# 05_Wireless.net
KiCad netlist of a schematic drawn in Altium Designer
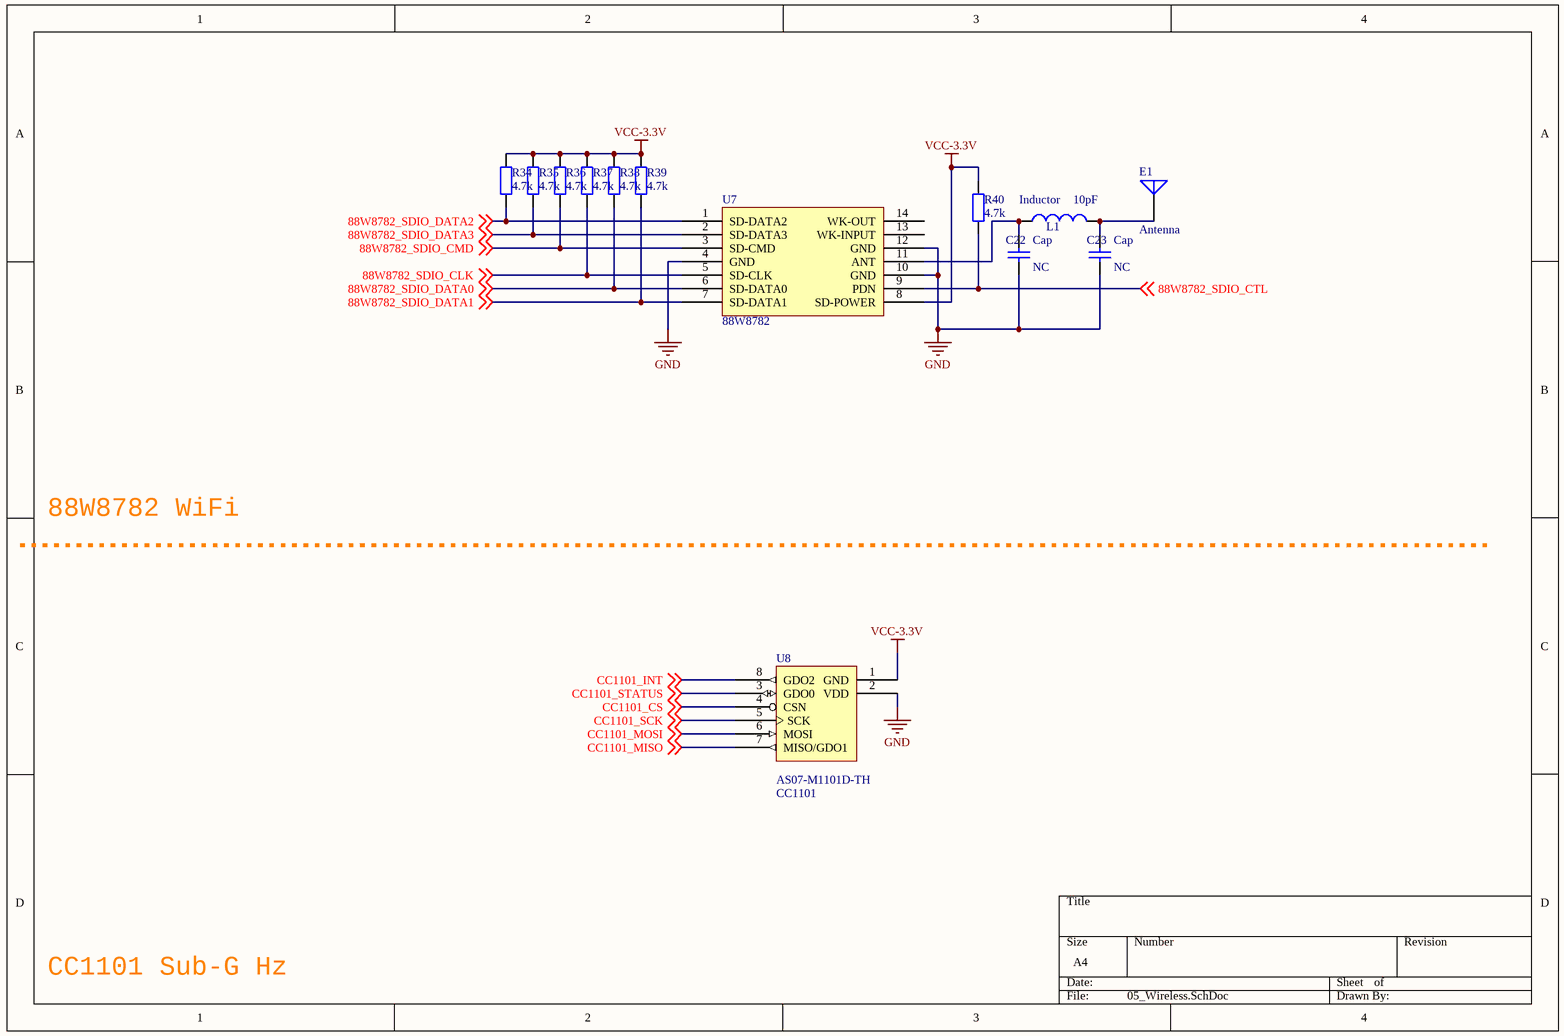
[diagram p0: 05_Wireless.SchDoc]

(export (version "E")
  (design (tool "Eeschema 10.0.6"))
  (components
    (comp (ref "C22")
      (value "Cap")
      (footprint "RAD-0.1")
      (description "Capacitor")
      (fields (field (name "ALTIUM_VALUE") "NC") (field (name "PUBLISHER") "Altium Limited"))
      (libsource (lib "Miscellaneous Devices") (part "Cap"))
    )
    (comp (ref "C23")
      (value "Cap")
      (footprint "RAD-0.1")
      (description "Capacitor")
      (fields (field (name "ALTIUM_VALUE") "NC") (field (name "PUBLISHER") "Altium Limited"))
      (libsource (lib "Miscellaneous Devices") (part "Cap"))
    )
    (comp (ref "E1")
      (value "Antenna")
      (footprint "ANT_MEANDER_LINE")
      (description "Generic Antenna")
      (fields (field (name "PUBLISHER") "Altium Limited"))
      (libsource (lib "Miscellaneous Devices") (part "Antenna"))
    )
    (comp (ref "L1")
      (value "Inductor")
      (footprint "0603")
      (fields (field (name "ALTIUM_VALUE") "10pF") (field (name "PUBLISHER") "Altium Limited"))
      (libsource (lib "Miscellaneous Devices") (part "Inductor"))
    )
    (comp (ref "R34")
      (value "4.7k")
      (footprint "AXIAL-0.3")
      (description "贴片电阻")
      (fields (field (name "Comment") "10k") (field (name "PUBLISHER") "Altium Limited"))
      (libsource (lib "fszhang") (part "Res1"))
    )
    (comp (ref "R35")
      (value "4.7k")
      (footprint "AXIAL-0.3")
      (description "贴片电阻")
      (fields (field (name "Comment") "10k") (field (name "PUBLISHER") "Altium Limited"))
      (libsource (lib "fszhang") (part "Res1"))
    )
    (comp (ref "R36")
      (value "4.7k")
      (footprint "AXIAL-0.3")
      (description "贴片电阻")
      (fields (field (name "Comment") "10k") (field (name "PUBLISHER") "Altium Limited"))
      (libsource (lib "fszhang") (part "Res1"))
    )
    (comp (ref "R37")
      (value "4.7k")
      (footprint "AXIAL-0.3")
      (description "贴片电阻")
      (fields (field (name "Comment") "10k") (field (name "PUBLISHER") "Altium Limited"))
      (libsource (lib "fszhang") (part "Res1"))
    )
    (comp (ref "R38")
      (value "4.7k")
      (footprint "AXIAL-0.3")
      (description "贴片电阻")
      (fields (field (name "Comment") "10k") (field (name "PUBLISHER") "Altium Limited"))
      (libsource (lib "fszhang") (part "Res1"))
    )
    (comp (ref "R39")
      (value "4.7k")
      (footprint "AXIAL-0.3")
      (description "贴片电阻")
      (fields (field (name "Comment") "10k") (field (name "PUBLISHER") "Altium Limited"))
      (libsource (lib "fszhang") (part "Res1"))
    )
    (comp (ref "R40")
      (value "4.7k")
      (footprint "AXIAL-0.3")
      (description "贴片电阻")
      (fields (field (name "Comment") "10k") (field (name "PUBLISHER") "Altium Limited"))
      (libsource (lib "fszhang") (part "Res1"))
    )
    (comp (ref "U7")
      (value "88W8782")
      (footprint "W8782")
      (description "802.11n Wireless Module")
      (libsource (lib "Miscellaneous Modules") (part "88W8782"))
    )
    (comp (ref "U8")
      (value "CC1101")
      (footprint "AS07-M1101D-TH")
      (fields
        (field (name "MANUFACTURER") "Texas Instruments (TI)")
        (field (name "MANUFACTURER PART NUMBER") "CC1101RGP")
      )
      (libsource (lib "Miscellaneous Modules") (part "CC1101"))
    )
  )
  (nets
    (net (code "1") (name "88W8782_SDIO_CLK") (class "Default")
      (node (ref "R37") (pin "1") (pinfunction "1_1") (pintype "passive"))
      (node (ref "U7") (pin "5") (pinfunction "SD-CLK_5") (pintype "passive"))
    )
    (net (code "2") (name "88W8782_SDIO_CMD") (class "Default")
      (node (ref "R36") (pin "1") (pinfunction "1_1") (pintype "passive"))
      (node (ref "U7") (pin "3") (pinfunction "SD-CMD_3") (pintype "passive"))
    )
    (net (code "3") (name "88W8782_SDIO_CTL") (class "Default")
      (node (ref "R40") (pin "1") (pinfunction "1_1") (pintype "passive"))
      (node (ref "U7") (pin "9") (pinfunction "PDN_9") (pintype "passive"))
    )
    (net (code "4") (name "88W8782_SDIO_DATA0") (class "Default")
      (node (ref "R38") (pin "1") (pinfunction "1_1") (pintype "passive"))
      (node (ref "U7") (pin "6") (pinfunction "SD-DATA0_6") (pintype "passive"))
    )
    (net (code "5") (name "88W8782_SDIO_DATA1") (class "Default")
      (node (ref "R39") (pin "1") (pinfunction "1_1") (pintype "passive"))
      (node (ref "U7") (pin "7") (pinfunction "SD-DATA1_7") (pintype "passive"))
    )
    (net (code "6") (name "88W8782_SDIO_DATA2") (class "Default")
      (node (ref "R34") (pin "1") (pinfunction "1_1") (pintype "passive"))
      (node (ref "U7") (pin "1") (pinfunction "SD-DATA2_1") (pintype "passive"))
    )
    (net (code "7") (name "88W8782_SDIO_DATA3") (class "Default")
      (node (ref "R35") (pin "1") (pinfunction "1_1") (pintype "passive"))
      (node (ref "U7") (pin "2") (pinfunction "SD-DATA3_2") (pintype "passive"))
    )
    (net (code "8") (name "CC1101_CS") (class "Default")
      (node (ref "U8") (pin "4") (pinfunction "CSN_4") (pintype "passive"))
    )
    (net (code "9") (name "CC1101_INT") (class "Default")
      (node (ref "U8") (pin "8") (pinfunction "GDO2_8") (pintype "output"))
    )
    (net (code "10") (name "CC1101_MISO") (class "Default")
      (node (ref "U8") (pin "7") (pinfunction "MISO/GDO1_7") (pintype "output"))
    )
    (net (code "11") (name "CC1101_MOSI") (class "Default")
      (node (ref "U8") (pin "6") (pinfunction "MOSI_6") (pintype "input"))
    )
    (net (code "12") (name "CC1101_SCK") (class "Default")
      (node (ref "U8") (pin "5") (pinfunction "SCK_5") (pintype "passive"))
    )
    (net (code "13") (name "CC1101_STATUS") (class "Default")
      (node (ref "U8") (pin "3") (pinfunction "GDO0_3") (pintype "bidirectional"))
    )
    (net (code "14") (name "GND") (class "Default")
      (node (ref "C22") (pin "1") (pinfunction "1_1") (pintype "passive"))
      (node (ref "C23") (pin "1") (pinfunction "1_1") (pintype "passive"))
      (node (ref "U7") (pin "10") (pinfunction "GND_10") (pintype "passive"))
      (node (ref "U7") (pin "12") (pinfunction "GND_12") (pintype "passive"))
      (node (ref "U7") (pin "4") (pinfunction "GND_4") (pintype "passive"))
      (node (ref "U8") (pin "2") (pinfunction "VDD_2") (pintype "passive"))
    )
    (net (code "15") (name "Net-(E1-A)") (class "Default")
      (node (ref "C23") (pin "2") (pinfunction "2_2") (pintype "passive"))
      (node (ref "E1") (pin "1") (pinfunction "A_1") (pintype "passive"))
      (node (ref "L1") (pin "2") (pinfunction "2_2") (pintype "passive"))
    )
    (net (code "16") (name "Net-(U7-ANT)") (class "Default")
      (node (ref "C22") (pin "2") (pinfunction "2_2") (pintype "passive"))
      (node (ref "L1") (pin "1") (pinfunction "1_1") (pintype "passive"))
      (node (ref "U7") (pin "11") (pinfunction "ANT_11") (pintype "passive"))
    )
    (net (code "17") (name "VCC-3.3V") (class "Default")
      (node (ref "R34") (pin "2") (pinfunction "2_2") (pintype "passive"))
      (node (ref "R35") (pin "2") (pinfunction "2_2") (pintype "passive"))
      (node (ref "R36") (pin "2") (pinfunction "2_2") (pintype "passive"))
      (node (ref "R37") (pin "2") (pinfunction "2_2") (pintype "passive"))
      (node (ref "R38") (pin "2") (pinfunction "2_2") (pintype "passive"))
      (node (ref "R39") (pin "2") (pinfunction "2_2") (pintype "passive"))
      (node (ref "R40") (pin "2") (pinfunction "2_2") (pintype "passive"))
      (node (ref "U7") (pin "8") (pinfunction "SD-POWER_8") (pintype "passive"))
      (node (ref "U8") (pin "1") (pinfunction "GND_1") (pintype "passive"))
    )
    (net (code "18") (name "unconnected-(U7-WK-INPUT-Pad13)") (class "Default")
      (node (ref "U7") (pin "13") (pinfunction "WK-INPUT_13") (pintype "passive"))
    )
    (net (code "19") (name "unconnected-(U7-WK-OUT-Pad14)") (class "Default")
      (node (ref "U7") (pin "14") (pinfunction "WK-OUT_14") (pintype "passive"))
    )
  )
)
